# current.net
KiCad netlist of a schematic drawn in EAGLE
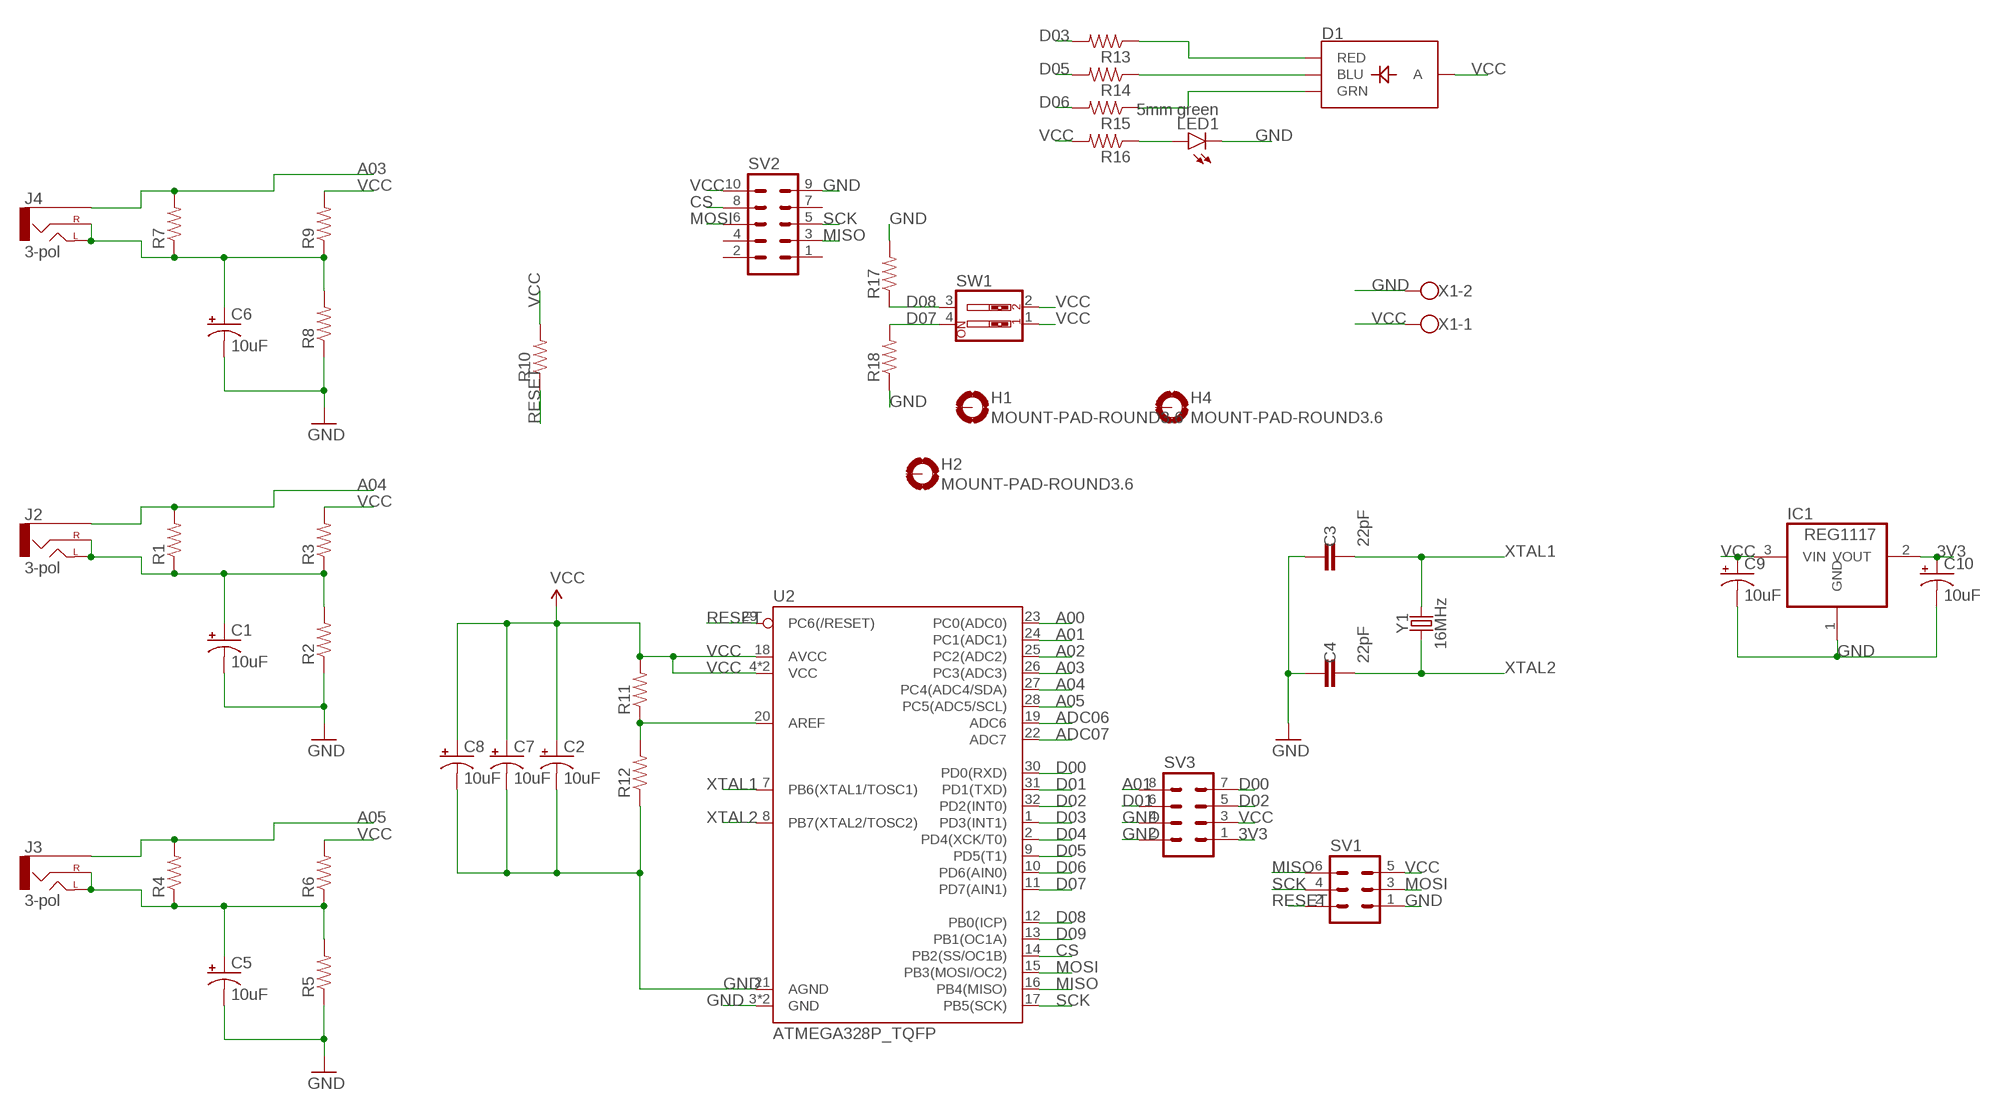
[diagram p0: schematic, sheet 1]

(export (version "E")
  (design (tool "Eeschema 10.0.6"))
  (components
    (comp (ref "C1")
      (value "10uF")
      (footprint "eagle-import:EIA3216")
      (libsource (lib "eagle-import") (part "10UF-POLAR-EIA3216-16V-10%(TANT)"))
    )
    (comp (ref "C2")
      (value "10uF")
      (footprint "eagle-import:EIA3216")
      (libsource (lib "eagle-import") (part "10UF-POLAR-EIA3216-16V-10%(TANT)"))
    )
    (comp (ref "C3")
      (value "22pF")
      (footprint "eagle-import:0805")
      (libsource (lib "eagle-import") (part "CAP-0805"))
    )
    (comp (ref "C4")
      (value "22pF")
      (footprint "eagle-import:0805")
      (libsource (lib "eagle-import") (part "CAP-0805"))
    )
    (comp (ref "C5")
      (value "10uF")
      (footprint "eagle-import:EIA3216")
      (libsource (lib "eagle-import") (part "10UF-POLAR-EIA3216-16V-10%(TANT)"))
    )
    (comp (ref "C6")
      (value "10uF")
      (footprint "eagle-import:EIA3216")
      (libsource (lib "eagle-import") (part "10UF-POLAR-EIA3216-16V-10%(TANT)"))
    )
    (comp (ref "C7")
      (value "10uF")
      (footprint "eagle-import:EIA3216")
      (libsource (lib "eagle-import") (part "10UF-POLAR-EIA3216-16V-10%(TANT)"))
    )
    (comp (ref "C8")
      (value "10uF")
      (footprint "eagle-import:EIA3216")
      (libsource (lib "eagle-import") (part "10UF-POLAR-EIA3216-16V-10%(TANT)"))
    )
    (comp (ref "C9")
      (value "10uF")
      (footprint "eagle-import:EIA3216")
      (libsource (lib "eagle-import") (part "10UF-POLAR-EIA3216-16V-10%(TANT)"))
    )
    (comp (ref "C10")
      (value "10uF")
      (footprint "eagle-import:EIA3216")
      (libsource (lib "eagle-import") (part "10UF-POLAR-EIA3216-16V-10%(TANT)"))
    )
    (comp (ref "D1")
      (value "LED-RGB-CASMD")
      (footprint "eagle-import:LED-TRICOLOR-SMD")
      (libsource (lib "eagle-import") (part "LED-RGB-CASMD"))
    )
    (comp (ref "H1")
      (value "MOUNT-PAD-ROUND3.6")
      (footprint "eagle-import:3,6-PAD")
      (libsource (lib "eagle-import") (part "MOUNT-PAD-ROUND3.6"))
    )
    (comp (ref "H2")
      (value "MOUNT-PAD-ROUND3.6")
      (footprint "eagle-import:3,6-PAD")
      (libsource (lib "eagle-import") (part "MOUNT-PAD-ROUND3.6"))
    )
    (comp (ref "H4")
      (value "MOUNT-PAD-ROUND3.6")
      (footprint "eagle-import:3,6-PAD")
      (libsource (lib "eagle-import") (part "MOUNT-PAD-ROUND3.6"))
    )
    (comp (ref "IC1")
      (value "REG1117")
      (footprint "eagle-import:SOT223")
      (libsource (lib "eagle-import") (part "REG1117"))
    )
    (comp (ref "J2")
      (value "3-pol")
      (footprint "eagle-import:AUDIO-JACK")
      (libsource (lib "eagle-import") (part "AUDIO-JACKPTH"))
    )
    (comp (ref "J3")
      (value "3-pol")
      (footprint "eagle-import:AUDIO-JACK")
      (libsource (lib "eagle-import") (part "AUDIO-JACKPTH"))
    )
    (comp (ref "J4")
      (value "3-pol")
      (footprint "eagle-import:AUDIO-JACK")
      (libsource (lib "eagle-import") (part "AUDIO-JACKPTH"))
    )
    (comp (ref "LED1")
      (value "5mm green")
      (footprint "eagle-import:CHIPLED_0805")
      (libsource (lib "eagle-import") (part "LEDCHIPLED_0805"))
    )
    (comp (ref "R1")
      (value "RESISTOR0805")
      (footprint "eagle-import:0805")
      (libsource (lib "eagle-import") (part "RESISTOR0805"))
    )
    (comp (ref "R2")
      (value "RESISTOR0805")
      (footprint "eagle-import:0805")
      (libsource (lib "eagle-import") (part "RESISTOR0805"))
    )
    (comp (ref "R3")
      (value "RESISTOR0805")
      (footprint "eagle-import:0805")
      (libsource (lib "eagle-import") (part "RESISTOR0805"))
    )
    (comp (ref "R4")
      (value "RESISTOR0805")
      (footprint "eagle-import:0805")
      (libsource (lib "eagle-import") (part "RESISTOR0805"))
    )
    (comp (ref "R5")
      (value "RESISTOR0805")
      (footprint "eagle-import:0805")
      (libsource (lib "eagle-import") (part "RESISTOR0805"))
    )
    (comp (ref "R6")
      (value "RESISTOR0805")
      (footprint "eagle-import:0805")
      (libsource (lib "eagle-import") (part "RESISTOR0805"))
    )
    (comp (ref "R7")
      (value "RESISTOR0805")
      (footprint "eagle-import:0805")
      (libsource (lib "eagle-import") (part "RESISTOR0805"))
    )
    (comp (ref "R8")
      (value "RESISTOR0805")
      (footprint "eagle-import:0805")
      (libsource (lib "eagle-import") (part "RESISTOR0805"))
    )
    (comp (ref "R9")
      (value "RESISTOR0805")
      (footprint "eagle-import:0805")
      (libsource (lib "eagle-import") (part "RESISTOR0805"))
    )
    (comp (ref "R10")
      (value "RESISTOR0805")
      (footprint "eagle-import:0805")
      (libsource (lib "eagle-import") (part "RESISTOR0805"))
    )
    (comp (ref "R11")
      (value "RESISTOR0805")
      (footprint "eagle-import:0805")
      (libsource (lib "eagle-import") (part "RESISTOR0805"))
    )
    (comp (ref "R12")
      (value "RESISTOR0805")
      (footprint "eagle-import:0805")
      (libsource (lib "eagle-import") (part "RESISTOR0805"))
    )
    (comp (ref "R13")
      (value "RESISTOR0805")
      (footprint "eagle-import:0805")
      (libsource (lib "eagle-import") (part "RESISTOR0805"))
    )
    (comp (ref "R14")
      (value "RESISTOR0805")
      (footprint "eagle-import:0805")
      (libsource (lib "eagle-import") (part "RESISTOR0805"))
    )
    (comp (ref "R15")
      (value "RESISTOR0805")
      (footprint "eagle-import:0805")
      (libsource (lib "eagle-import") (part "RESISTOR0805"))
    )
    (comp (ref "R16")
      (value "RESISTOR0805")
      (footprint "eagle-import:0805")
      (libsource (lib "eagle-import") (part "RESISTOR0805"))
    )
    (comp (ref "R17")
      (value "RESISTOR0805")
      (footprint "eagle-import:0805")
      (libsource (lib "eagle-import") (part "RESISTOR0805"))
    )
    (comp (ref "R18")
      (value "RESISTOR0805")
      (footprint "eagle-import:0805")
      (libsource (lib "eagle-import") (part "RESISTOR0805"))
    )
    (comp (ref "SV1")
      (value "MA03-2")
      (footprint "eagle-import:MA03-2")
      (libsource (lib "eagle-import") (part "MA03-2"))
    )
    (comp (ref "SV2")
      (value "MA05-2")
      (footprint "eagle-import:MA05-2")
      (libsource (lib "eagle-import") (part "MA05-2"))
    )
    (comp (ref "SV3")
      (value "MA04-2")
      (footprint "eagle-import:MA04-2")
      (libsource (lib "eagle-import") (part "MA04-2"))
    )
    (comp (ref "SW1")
      (value "SW_DIP-2")
      (footprint "eagle-import:EDG-02")
      (libsource (lib "eagle-import") (part "SW_DIP-2"))
    )
    (comp (ref "U2")
      (value "ATMEGA328P_TQFP")
      (footprint "eagle-import:TQFP32-08")
      (libsource (lib "eagle-import") (part "ATMEGA328P_TQFP"))
    )
    (comp (ref "X1")
      (value "W237-102")
      (footprint "eagle-import:W237-102")
      (fields (field (name "MPN") "237-102"))
      (libsource (lib "eagle-import") (part "W237-102"))
    )
    (comp (ref "Y1")
      (value "16MHz")
      (footprint "eagle-import:CRYSTAL-SMD-3.2X2.5MM")
      (libsource (lib "eagle-import") (part "CRYSTALSMD-3.2X2.5"))
    )
  )
  (nets
    (net (code "1") (name "/3V3") (class "Default")
      (node (ref "C10") (pin "+") (pinfunction "+_+") (pintype "passive"))
      (node (ref "IC1") (pin "2") (pinfunction "VOUT_2") (pintype "output"))
      (node (ref "SV3") (pin "1") (pinfunction "1_1") (pintype "passive"))
    )
    (net (code "2") (name "/A00") (class "Default")
      (node (ref "U2") (pin "23") (pinfunction "PC0(ADC0)_23") (pintype "bidirectional"))
    )
    (net (code "3") (name "/A01") (class "Default")
      (node (ref "SV3") (pin "8") (pinfunction "8_8") (pintype "passive"))
      (node (ref "U2") (pin "24") (pinfunction "PC1(ADC1)_24") (pintype "bidirectional"))
    )
    (net (code "4") (name "/A02") (class "Default")
      (node (ref "U2") (pin "25") (pinfunction "PC2(ADC2)_25") (pintype "bidirectional"))
    )
    (net (code "5") (name "/A03") (class "Default")
      (node (ref "J4") (pin "SLEEVE") (pinfunction "SLEEVE_SLEEVE") (pintype "bidirectional"))
      (node (ref "R7") (pin "2") (pinfunction "2_2") (pintype "passive"))
      (node (ref "U2") (pin "26") (pinfunction "PC3(ADC3)_26") (pintype "bidirectional"))
    )
    (net (code "6") (name "/A04") (class "Default")
      (node (ref "J2") (pin "SLEEVE") (pinfunction "SLEEVE_SLEEVE") (pintype "bidirectional"))
      (node (ref "R1") (pin "2") (pinfunction "2_2") (pintype "passive"))
      (node (ref "U2") (pin "27") (pinfunction "PC4(ADC4/SDA)_27") (pintype "bidirectional"))
    )
    (net (code "7") (name "/A05") (class "Default")
      (node (ref "J3") (pin "SLEEVE") (pinfunction "SLEEVE_SLEEVE") (pintype "bidirectional"))
      (node (ref "R4") (pin "2") (pinfunction "2_2") (pintype "passive"))
      (node (ref "U2") (pin "28") (pinfunction "PC5(ADC5/SCL)_28") (pintype "bidirectional"))
    )
    (net (code "8") (name "/ADC06") (class "Default")
      (node (ref "U2") (pin "19") (pinfunction "ADC6_19") (pintype "bidirectional"))
    )
    (net (code "9") (name "/ADC07") (class "Default")
      (node (ref "U2") (pin "22") (pinfunction "ADC7_22") (pintype "bidirectional"))
    )
    (net (code "10") (name "/CS") (class "Default")
      (node (ref "SV2") (pin "8") (pinfunction "8_8") (pintype "passive"))
      (node (ref "U2") (pin "14") (pinfunction "PB2(SS/OC1B)_14") (pintype "bidirectional"))
    )
    (net (code "11") (name "/D00") (class "Default")
      (node (ref "SV3") (pin "7") (pinfunction "7_7") (pintype "passive"))
      (node (ref "U2") (pin "30") (pinfunction "PD0(RXD)_30") (pintype "bidirectional"))
    )
    (net (code "12") (name "/D01") (class "Default")
      (node (ref "SV3") (pin "6") (pinfunction "6_6") (pintype "passive"))
      (node (ref "U2") (pin "31") (pinfunction "PD1(TXD)_31") (pintype "bidirectional"))
    )
    (net (code "13") (name "/D02") (class "Default")
      (node (ref "SV3") (pin "5") (pinfunction "5_5") (pintype "passive"))
      (node (ref "U2") (pin "32") (pinfunction "PD2(INT0)_32") (pintype "bidirectional"))
    )
    (net (code "14") (name "/D03") (class "Default")
      (node (ref "R13") (pin "2") (pinfunction "2_2") (pintype "passive"))
      (node (ref "U2") (pin "1") (pinfunction "PD3(INT1)_1") (pintype "bidirectional"))
    )
    (net (code "15") (name "/D04") (class "Default")
      (node (ref "U2") (pin "2") (pinfunction "PD4(XCK/T0)_2") (pintype "bidirectional"))
    )
    (net (code "16") (name "/D05") (class "Default")
      (node (ref "R14") (pin "2") (pinfunction "2_2") (pintype "passive"))
      (node (ref "U2") (pin "9") (pinfunction "PD5(T1)_9") (pintype "bidirectional"))
    )
    (net (code "17") (name "/D06") (class "Default")
      (node (ref "R15") (pin "2") (pinfunction "2_2") (pintype "passive"))
      (node (ref "U2") (pin "10") (pinfunction "PD6(AIN0)_10") (pintype "bidirectional"))
    )
    (net (code "18") (name "/D07") (class "Default")
      (node (ref "R18") (pin "2") (pinfunction "2_2") (pintype "passive"))
      (node (ref "SW1") (pin "4") (pinfunction "4_4") (pintype "passive"))
      (node (ref "U2") (pin "11") (pinfunction "PD7(AIN1)_11") (pintype "bidirectional"))
    )
    (net (code "19") (name "/D08") (class "Default")
      (node (ref "R17") (pin "1") (pinfunction "1_1") (pintype "passive"))
      (node (ref "SW1") (pin "3") (pinfunction "3_3") (pintype "passive"))
      (node (ref "U2") (pin "12") (pinfunction "PB0(ICP)_12") (pintype "bidirectional"))
    )
    (net (code "20") (name "/D09") (class "Default")
      (node (ref "U2") (pin "13") (pinfunction "PB1(OC1A)_13") (pintype "bidirectional"))
    )
    (net (code "21") (name "/MISO") (class "Default")
      (node (ref "SV1") (pin "6") (pinfunction "6_6") (pintype "passive"))
      (node (ref "SV2") (pin "3") (pinfunction "3_3") (pintype "passive"))
      (node (ref "U2") (pin "16") (pinfunction "PB4(MISO)_16") (pintype "bidirectional"))
    )
    (net (code "22") (name "/MOSI") (class "Default")
      (node (ref "SV1") (pin "3") (pinfunction "3_3") (pintype "passive"))
      (node (ref "SV2") (pin "6") (pinfunction "6_6") (pintype "passive"))
      (node (ref "U2") (pin "15") (pinfunction "PB3(MOSI/OC2)_15") (pintype "bidirectional"))
    )
    (net (code "23") (name "/RESET") (class "Default")
      (node (ref "R10") (pin "1") (pinfunction "1_1") (pintype "passive"))
      (node (ref "SV1") (pin "2") (pinfunction "2_2") (pintype "passive"))
      (node (ref "U2") (pin "29") (pinfunction "PC6(/RESET)_29") (pintype "bidirectional"))
    )
    (net (code "24") (name "/SCK") (class "Default")
      (node (ref "SV1") (pin "4") (pinfunction "4_4") (pintype "passive"))
      (node (ref "SV2") (pin "5") (pinfunction "5_5") (pintype "passive"))
      (node (ref "U2") (pin "17") (pinfunction "PB5(SCK)_17") (pintype "bidirectional"))
    )
    (net (code "25") (name "/XTAL1") (class "Default")
      (node (ref "C3") (pin "2") (pinfunction "2_2") (pintype "passive"))
      (node (ref "U2") (pin "7") (pinfunction "PB6(XTAL1/TOSC1)_7") (pintype "bidirectional"))
      (node (ref "Y1") (pin "3") (pinfunction "2_3") (pintype "passive"))
    )
    (net (code "26") (name "/XTAL2") (class "Default")
      (node (ref "C4") (pin "2") (pinfunction "2_2") (pintype "passive"))
      (node (ref "U2") (pin "8") (pinfunction "PB7(XTAL2/TOSC2)_8") (pintype "bidirectional"))
      (node (ref "Y1") (pin "1") (pinfunction "1_1") (pintype "passive"))
    )
    (net (code "27") (name "GND") (class "Default")
      (node (ref "C1") (pin "-") (pinfunction "-_-") (pintype "passive"))
      (node (ref "C10") (pin "-") (pinfunction "-_-") (pintype "passive"))
      (node (ref "C2") (pin "-") (pinfunction "-_-") (pintype "passive"))
      (node (ref "C3") (pin "1") (pinfunction "1_1") (pintype "passive"))
      (node (ref "C4") (pin "1") (pinfunction "1_1") (pintype "passive"))
      (node (ref "C5") (pin "-") (pinfunction "-_-") (pintype "passive"))
      (node (ref "C6") (pin "-") (pinfunction "-_-") (pintype "passive"))
      (node (ref "C7") (pin "-") (pinfunction "-_-") (pintype "passive"))
      (node (ref "C8") (pin "-") (pinfunction "-_-") (pintype "passive"))
      (node (ref "C9") (pin "-") (pinfunction "-_-") (pintype "passive"))
      (node (ref "IC1") (pin "1") (pinfunction "GND_1") (pintype "power_in"))
      (node (ref "LED1") (pin "C") (pinfunction "C_C") (pintype "passive"))
      (node (ref "R12") (pin "1") (pinfunction "1_1") (pintype "passive"))
      (node (ref "R17") (pin "2") (pinfunction "2_2") (pintype "passive"))
      (node (ref "R18") (pin "1") (pinfunction "1_1") (pintype "passive"))
      (node (ref "R2") (pin "1") (pinfunction "1_1") (pintype "passive"))
      (node (ref "R5") (pin "1") (pinfunction "1_1") (pintype "passive"))
      (node (ref "R8") (pin "1") (pinfunction "1_1") (pintype "passive"))
      (node (ref "SV1") (pin "1") (pinfunction "1_1") (pintype "passive"))
      (node (ref "SV2") (pin "9") (pinfunction "9_9") (pintype "passive"))
      (node (ref "SV3") (pin "2") (pinfunction "2_2") (pintype "passive"))
      (node (ref "SV3") (pin "4") (pinfunction "4_4") (pintype "passive"))
      (node (ref "U2") (pin "21") (pinfunction "AGND_21") (pintype "bidirectional"))
      (node (ref "U2") (pin "3") (pinfunction "GND_3") (pintype "bidirectional"))
      (node (ref "U2") (pin "5") (pinfunction "GND_5") (pintype "bidirectional"))
      (node (ref "X1") (pin "2") (pinfunction "KL_2") (pintype "passive"))
    )
    (net (code "28") (name "Net-(D1-BLU)") (class "Default")
      (node (ref "D1") (pin "B") (pinfunction "BLU_B") (pintype "bidirectional"))
      (node (ref "R14") (pin "1") (pinfunction "1_1") (pintype "passive"))
    )
    (net (code "29") (name "Net-(D1-GRN)") (class "Default")
      (node (ref "D1") (pin "G") (pinfunction "GRN_G") (pintype "bidirectional"))
      (node (ref "R15") (pin "1") (pinfunction "1_1") (pintype "passive"))
    )
    (net (code "30") (name "Net-(D1-RED)") (class "Default")
      (node (ref "D1") (pin "R") (pinfunction "RED_R") (pintype "bidirectional"))
      (node (ref "R13") (pin "1") (pinfunction "1_1") (pintype "passive"))
    )
    (net (code "31") (name "Net-(J2-LEFT)") (class "Default")
      (node (ref "C1") (pin "+") (pinfunction "+_+") (pintype "passive"))
      (node (ref "J2") (pin "RING") (pinfunction "RIGHT_RING") (pintype "bidirectional"))
      (node (ref "J2") (pin "TIP") (pinfunction "LEFT_TIP") (pintype "bidirectional"))
      (node (ref "R1") (pin "1") (pinfunction "1_1") (pintype "passive"))
      (node (ref "R2") (pin "2") (pinfunction "2_2") (pintype "passive"))
      (node (ref "R3") (pin "1") (pinfunction "1_1") (pintype "passive"))
    )
    (net (code "32") (name "Net-(J3-LEFT)") (class "Default")
      (node (ref "C5") (pin "+") (pinfunction "+_+") (pintype "passive"))
      (node (ref "J3") (pin "RING") (pinfunction "RIGHT_RING") (pintype "bidirectional"))
      (node (ref "J3") (pin "TIP") (pinfunction "LEFT_TIP") (pintype "bidirectional"))
      (node (ref "R4") (pin "1") (pinfunction "1_1") (pintype "passive"))
      (node (ref "R5") (pin "2") (pinfunction "2_2") (pintype "passive"))
      (node (ref "R6") (pin "1") (pinfunction "1_1") (pintype "passive"))
    )
    (net (code "33") (name "Net-(J4-LEFT)") (class "Default")
      (node (ref "C6") (pin "+") (pinfunction "+_+") (pintype "passive"))
      (node (ref "J4") (pin "RING") (pinfunction "RIGHT_RING") (pintype "bidirectional"))
      (node (ref "J4") (pin "TIP") (pinfunction "LEFT_TIP") (pintype "bidirectional"))
      (node (ref "R7") (pin "1") (pinfunction "1_1") (pintype "passive"))
      (node (ref "R8") (pin "2") (pinfunction "2_2") (pintype "passive"))
      (node (ref "R9") (pin "1") (pinfunction "1_1") (pintype "passive"))
    )
    (net (code "34") (name "Net-(LED1-PadA)") (class "Default")
      (node (ref "LED1") (pin "A") (pinfunction "A_A") (pintype "passive"))
      (node (ref "R16") (pin "1") (pinfunction "1_1") (pintype "passive"))
    )
    (net (code "35") (name "Net-(U2-AREF)") (class "Default")
      (node (ref "R11") (pin "1") (pinfunction "1_1") (pintype "passive"))
      (node (ref "R12") (pin "2") (pinfunction "2_2") (pintype "passive"))
      (node (ref "U2") (pin "20") (pinfunction "AREF_20") (pintype "bidirectional"))
    )
    (net (code "36") (name "VCC") (class "Default")
      (node (ref "C2") (pin "+") (pinfunction "+_+") (pintype "passive"))
      (node (ref "C7") (pin "+") (pinfunction "+_+") (pintype "passive"))
      (node (ref "C8") (pin "+") (pinfunction "+_+") (pintype "passive"))
      (node (ref "C9") (pin "+") (pinfunction "+_+") (pintype "passive"))
      (node (ref "D1") (pin "A") (pinfunction "A_A") (pintype "bidirectional"))
      (node (ref "IC1") (pin "3") (pinfunction "VIN_3") (pintype "input"))
      (node (ref "R10") (pin "2") (pinfunction "2_2") (pintype "passive"))
      (node (ref "R11") (pin "2") (pinfunction "2_2") (pintype "passive"))
      (node (ref "R16") (pin "2") (pinfunction "2_2") (pintype "passive"))
      (node (ref "R3") (pin "2") (pinfunction "2_2") (pintype "passive"))
      (node (ref "R6") (pin "2") (pinfunction "2_2") (pintype "passive"))
      (node (ref "R9") (pin "2") (pinfunction "2_2") (pintype "passive"))
      (node (ref "SV1") (pin "5") (pinfunction "5_5") (pintype "passive"))
      (node (ref "SV2") (pin "10") (pinfunction "10_10") (pintype "passive"))
      (node (ref "SV3") (pin "3") (pinfunction "3_3") (pintype "passive"))
      (node (ref "SW1") (pin "1") (pinfunction "1_1") (pintype "passive"))
      (node (ref "SW1") (pin "2") (pinfunction "2_2") (pintype "passive"))
      (node (ref "U2") (pin "18") (pinfunction "AVCC_18") (pintype "bidirectional"))
      (node (ref "U2") (pin "4") (pinfunction "VCC_4") (pintype "bidirectional"))
      (node (ref "U2") (pin "6") (pinfunction "VCC_6") (pintype "bidirectional"))
      (node (ref "X1") (pin "1") (pinfunction "KL_1") (pintype "passive"))
    )
    (net (code "37") (name "unconnected-(H1-MOUNT-PadB3,6)") (class "Default")
      (node (ref "H1") (pin "B3,6") (pinfunction "MOUNT_B3,6") (pintype "passive"))
    )
    (net (code "38") (name "unconnected-(H2-MOUNT-PadB3,6)") (class "Default")
      (node (ref "H2") (pin "B3,6") (pinfunction "MOUNT_B3,6") (pintype "passive"))
    )
    (net (code "39") (name "unconnected-(H4-MOUNT-PadB3,6)") (class "Default")
      (node (ref "H4") (pin "B3,6") (pinfunction "MOUNT_B3,6") (pintype "passive"))
    )
    (net (code "40") (name "unconnected-(SV2-Pad1)") (class "Default")
      (node (ref "SV2") (pin "1") (pinfunction "1_1") (pintype "passive"))
    )
    (net (code "41") (name "unconnected-(SV2-Pad2)") (class "Default")
      (node (ref "SV2") (pin "2") (pinfunction "2_2") (pintype "passive"))
    )
    (net (code "42") (name "unconnected-(SV2-Pad4)") (class "Default")
      (node (ref "SV2") (pin "4") (pinfunction "4_4") (pintype "passive"))
    )
    (net (code "43") (name "unconnected-(SV2-Pad7)") (class "Default")
      (node (ref "SV2") (pin "7") (pinfunction "7_7") (pintype "passive"))
    )
  )
)
